# atdh1150usb.net
KiCad netlist of a schematic drawn in EAGLE
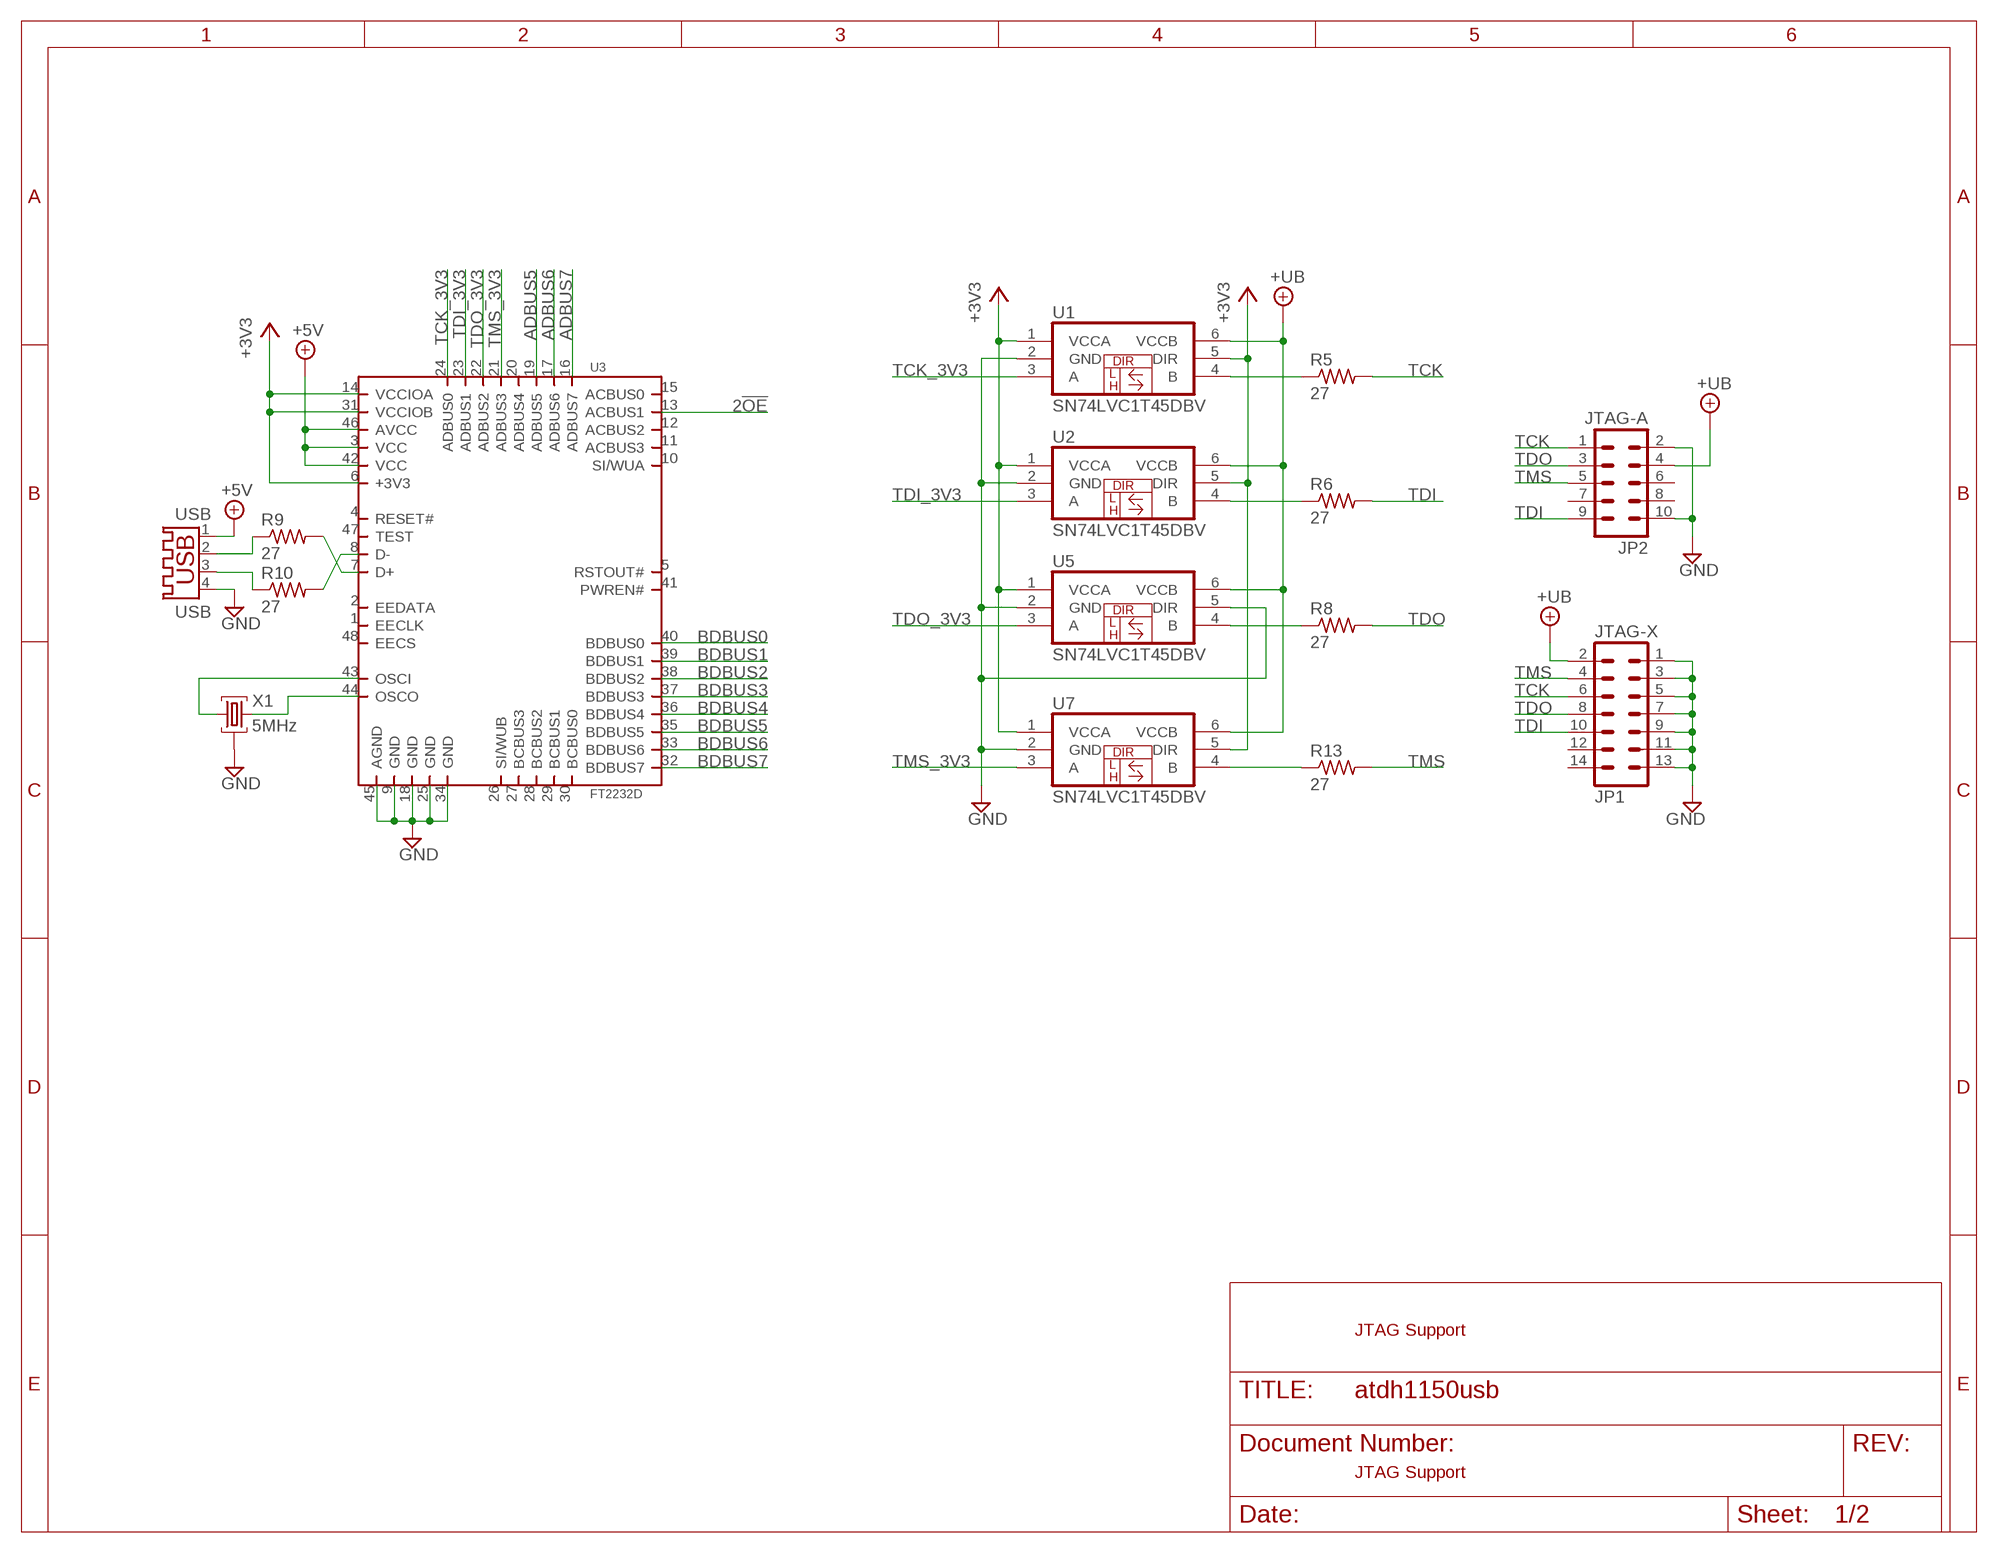
[diagram p0: schematic, sheet 1]
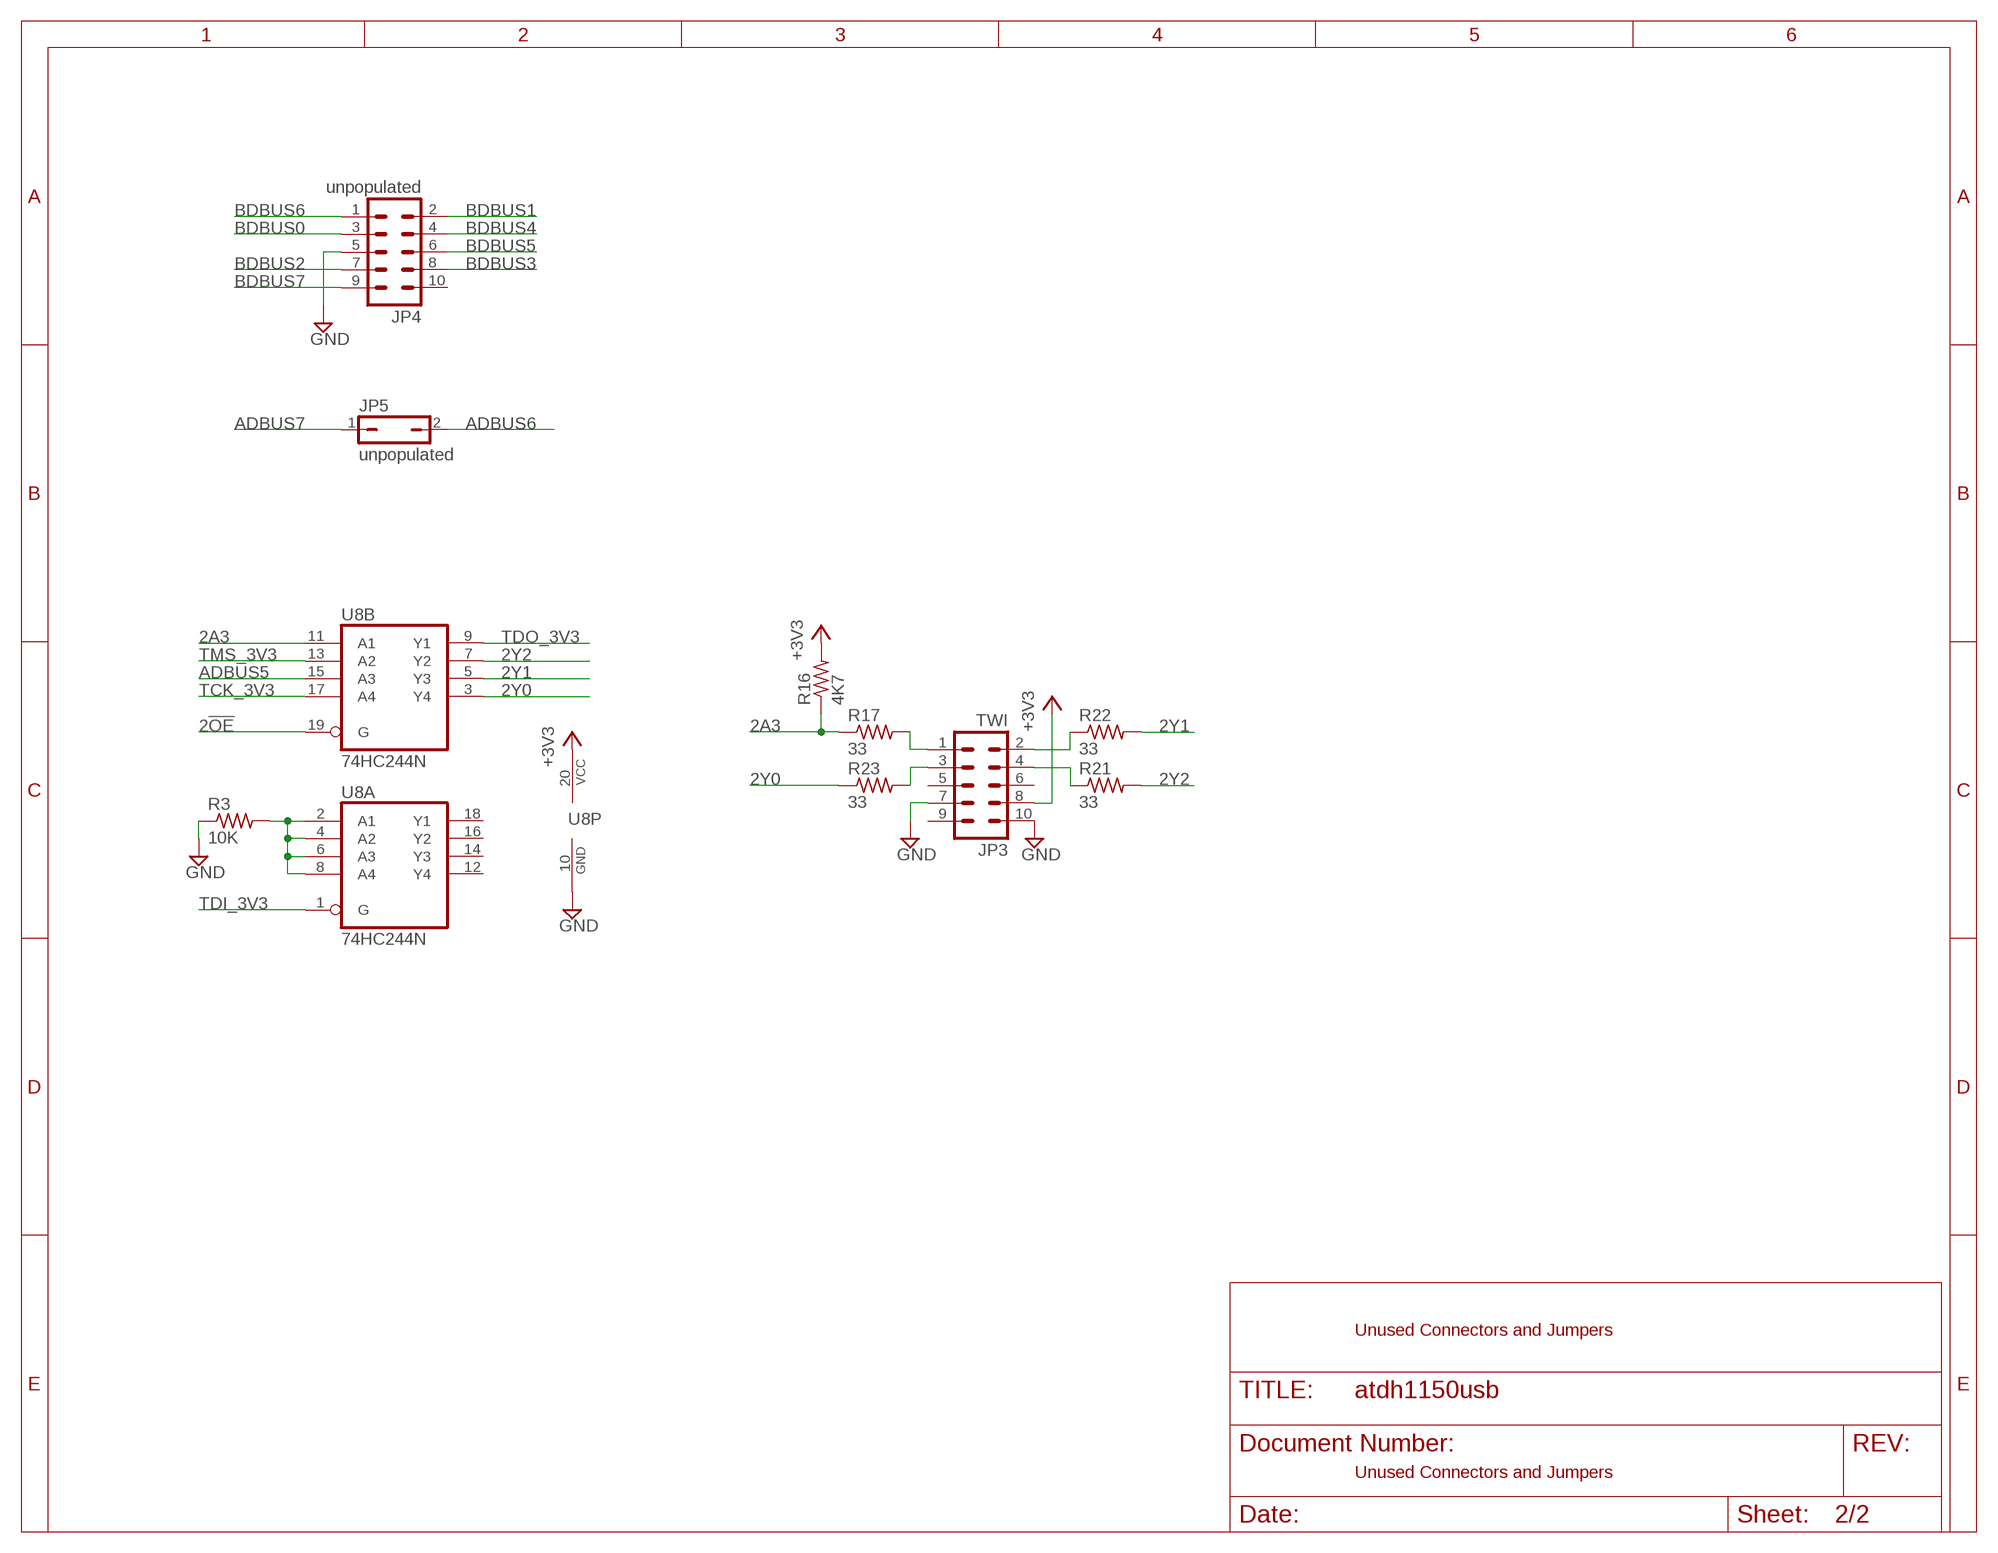
[diagram p1: schematic, sheet 2]

(export (version "E")
  (design (tool "Eeschema 10.0.6"))
  (components
    (comp (ref "JP1")
      (value "JTAG-X")
      (footprint "eagle-import:ML14")
      (libsource (lib "eagle-import") (part "ML14"))
    )
    (comp (ref "JP2")
      (value "JTAG-A")
      (footprint "eagle-import:ML10")
      (libsource (lib "eagle-import") (part "ML10"))
    )
    (comp (ref "R5")
      (value "27")
      (footprint "eagle-import:R0805")
      (libsource (lib "eagle-import") (part "R-US_R0805"))
    )
    (comp (ref "R6")
      (value "27")
      (footprint "eagle-import:R0805")
      (libsource (lib "eagle-import") (part "R-US_R0805"))
    )
    (comp (ref "R8")
      (value "27")
      (footprint "eagle-import:R0805")
      (libsource (lib "eagle-import") (part "R-US_R0805"))
    )
    (comp (ref "R9")
      (value "27")
      (footprint "eagle-import:R0805")
      (libsource (lib "eagle-import") (part "R-US_R0805"))
    )
    (comp (ref "R10")
      (value "27")
      (footprint "eagle-import:R0805")
      (libsource (lib "eagle-import") (part "R-US_R0805"))
    )
    (comp (ref "R13")
      (value "27")
      (footprint "eagle-import:R0805")
      (libsource (lib "eagle-import") (part "R-US_R0805"))
    )
    (comp (ref "U1")
      (value "SN74LVC1T45DBV")
      (footprint "eagle-import:DBV-R-PDSO-G6")
      (libsource (lib "eagle-import") (part "IC_BUFF_SN74LVC1T45DBV"))
    )
    (comp (ref "U2")
      (value "SN74LVC1T45DBV")
      (footprint "eagle-import:DBV-R-PDSO-G6")
      (libsource (lib "eagle-import") (part "IC_BUFF_SN74LVC1T45DBV"))
    )
    (comp (ref "U3")
      (value "FT2232D")
      (footprint "eagle-import:LQFP48")
      (libsource (lib "eagle-import") (part "FT2232D"))
    )
    (comp (ref "U5")
      (value "SN74LVC1T45DBV")
      (footprint "eagle-import:DBV-R-PDSO-G6")
      (libsource (lib "eagle-import") (part "IC_BUFF_SN74LVC1T45DBV"))
    )
    (comp (ref "U7")
      (value "SN74LVC1T45DBV")
      (footprint "eagle-import:DBV-R-PDSO-G6")
      (libsource (lib "eagle-import") (part "IC_BUFF_SN74LVC1T45DBV"))
    )
    (comp (ref "USB")
      (value "USB")
      (footprint "eagle-import:USB-A003")
      (libsource (lib "eagle-import") (part "USB-A003"))
    )
    (comp (ref "X1")
      (value "5MHz")
      (footprint "eagle-import:HC49U")
      (libsource (lib "eagle-import") (part "8M10AHC49T"))
    )
    (comp (ref "JP3")
      (value "TWI")
      (footprint "eagle-import:ML10")
      (libsource (lib "eagle-import") (part "ML10"))
    )
    (comp (ref "JP4")
      (value "unpopulated")
      (footprint "eagle-import:ML10")
      (libsource (lib "eagle-import") (part "ML10"))
    )
    (comp (ref "JP5")
      (value "unpopulated")
      (footprint "eagle-import:JP1")
      (libsource (lib "eagle-import") (part "JP1Q"))
    )
    (comp (ref "R3")
      (value "10K")
      (footprint "eagle-import:R0805")
      (libsource (lib "eagle-import") (part "R-US_R0805"))
    )
    (comp (ref "R16")
      (value "4K7")
      (footprint "eagle-import:R0805")
      (libsource (lib "eagle-import") (part "R-US_R0805"))
    )
    (comp (ref "R17")
      (value "33")
      (footprint "eagle-import:R0805")
      (libsource (lib "eagle-import") (part "R-US_R0805"))
    )
    (comp (ref "R21")
      (value "33")
      (footprint "eagle-import:R0805")
      (libsource (lib "eagle-import") (part "R-US_R0805"))
    )
    (comp (ref "R22")
      (value "33")
      (footprint "eagle-import:R0805")
      (libsource (lib "eagle-import") (part "R-US_R0805"))
    )
    (comp (ref "R23")
      (value "33")
      (footprint "eagle-import:R0805")
      (libsource (lib "eagle-import") (part "R-US_R0805"))
    )
    (comp (ref "U8")
      (value "74HC244N")
      (footprint "eagle-import:DIL20")
      (libsource (lib "eagle-import") (part "74244NLS"))
    )
  )
  (nets
    (net (code "1") (name "+3V3") (class "Default")
      (node (ref "JP3") (pin "8") (pinfunction "8_8") (pintype "passive"))
      (node (ref "R16") (pin "2") (pinfunction "2_2") (pintype "passive"))
      (node (ref "U1") (pin "1") (pinfunction "VCCA_1") (pintype "power_in"))
      (node (ref "U1") (pin "5") (pinfunction "DIR_5") (pintype "input"))
      (node (ref "U2") (pin "1") (pinfunction "VCCA_1") (pintype "power_in"))
      (node (ref "U2") (pin "5") (pinfunction "DIR_5") (pintype "input"))
      (node (ref "U3") (pin "14") (pinfunction "VCCIOA_14") (pintype "power_in"))
      (node (ref "U3") (pin "31") (pinfunction "VCCIOB_31") (pintype "power_in"))
      (node (ref "U3") (pin "6") (pinfunction "+3V3_6") (pintype "power_in"))
      (node (ref "U5") (pin "1") (pinfunction "VCCA_1") (pintype "power_in"))
      (node (ref "U7") (pin "1") (pinfunction "VCCA_1") (pintype "power_in"))
      (node (ref "U7") (pin "5") (pinfunction "DIR_5") (pintype "input"))
      (node (ref "U8") (pin "20") (pinfunction "VCC_20") (pintype "power_in"))
    )
    (net (code "2") (name "+5V") (class "Default")
      (node (ref "U3") (pin "3") (pinfunction "VCC_3") (pintype "power_in"))
      (node (ref "U3") (pin "42") (pinfunction "VCC_42") (pintype "power_in"))
      (node (ref "U3") (pin "46") (pinfunction "AVCC_46") (pintype "power_in"))
      (node (ref "USB") (pin "1") (pinfunction "1_1") (pintype "passive"))
    )
    (net (code "3") (name "+UB") (class "Default")
      (node (ref "JP1") (pin "2") (pinfunction "2_2") (pintype "passive"))
      (node (ref "JP2") (pin "4") (pinfunction "4_4") (pintype "passive"))
      (node (ref "U1") (pin "6") (pinfunction "VCCB_6") (pintype "power_in"))
      (node (ref "U2") (pin "6") (pinfunction "VCCB_6") (pintype "power_in"))
      (node (ref "U5") (pin "6") (pinfunction "VCCB_6") (pintype "power_in"))
      (node (ref "U7") (pin "6") (pinfunction "VCCB_6") (pintype "power_in"))
    )
    (net (code "4") (name "2A3") (class "Default")
      (node (ref "R16") (pin "1") (pinfunction "1_1") (pintype "passive"))
      (node (ref "R17") (pin "1") (pinfunction "1_1") (pintype "passive"))
      (node (ref "U8") (pin "11") (pinfunction "A1_11") (pintype "input"))
    )
    (net (code "5") (name "2Y0") (class "Default")
      (node (ref "R23") (pin "1") (pinfunction "1_1") (pintype "passive"))
      (node (ref "U8") (pin "3") (pinfunction "Y4_3") (pintype "tri_state"))
    )
    (net (code "6") (name "2Y1") (class "Default")
      (node (ref "R22") (pin "2") (pinfunction "2_2") (pintype "passive"))
      (node (ref "U8") (pin "5") (pinfunction "Y3_5") (pintype "tri_state"))
    )
    (net (code "7") (name "2Y2") (class "Default")
      (node (ref "R21") (pin "2") (pinfunction "2_2") (pintype "passive"))
      (node (ref "U8") (pin "7") (pinfunction "Y2_7") (pintype "tri_state"))
    )
    (net (code "8") (name "2~{OE}") (class "Default")
      (node (ref "U3") (pin "13") (pinfunction "ACBUS1_13") (pintype "bidirectional"))
      (node (ref "U8") (pin "19") (pinfunction "G_19") (pintype "input"))
    )
    (net (code "9") (name "ADBUS5") (class "Default")
      (node (ref "U3") (pin "19") (pinfunction "ADBUS5_19") (pintype "bidirectional"))
      (node (ref "U8") (pin "15") (pinfunction "A3_15") (pintype "input"))
    )
    (net (code "10") (name "ADBUS6") (class "Default")
      (node (ref "JP5") (pin "2") (pinfunction "2_2") (pintype "passive"))
      (node (ref "U3") (pin "17") (pinfunction "ADBUS6_17") (pintype "bidirectional"))
    )
    (net (code "11") (name "ADBUS7") (class "Default")
      (node (ref "JP5") (pin "1") (pinfunction "1_1") (pintype "passive"))
      (node (ref "U3") (pin "16") (pinfunction "ADBUS7_16") (pintype "bidirectional"))
    )
    (net (code "12") (name "BDBUS0") (class "Default")
      (node (ref "JP4") (pin "3") (pinfunction "3_3") (pintype "passive"))
      (node (ref "U3") (pin "40") (pinfunction "BDBUS0_40") (pintype "bidirectional"))
    )
    (net (code "13") (name "BDBUS1") (class "Default")
      (node (ref "JP4") (pin "2") (pinfunction "2_2") (pintype "passive"))
      (node (ref "U3") (pin "39") (pinfunction "BDBUS1_39") (pintype "bidirectional"))
    )
    (net (code "14") (name "BDBUS2") (class "Default")
      (node (ref "JP4") (pin "7") (pinfunction "7_7") (pintype "passive"))
      (node (ref "U3") (pin "38") (pinfunction "BDBUS2_38") (pintype "bidirectional"))
    )
    (net (code "15") (name "BDBUS3") (class "Default")
      (node (ref "JP4") (pin "8") (pinfunction "8_8") (pintype "passive"))
      (node (ref "U3") (pin "37") (pinfunction "BDBUS3_37") (pintype "bidirectional"))
    )
    (net (code "16") (name "BDBUS4") (class "Default")
      (node (ref "JP4") (pin "4") (pinfunction "4_4") (pintype "passive"))
      (node (ref "U3") (pin "36") (pinfunction "BDBUS4_36") (pintype "bidirectional"))
    )
    (net (code "17") (name "BDBUS5") (class "Default")
      (node (ref "JP4") (pin "6") (pinfunction "6_6") (pintype "passive"))
      (node (ref "U3") (pin "35") (pinfunction "BDBUS5_35") (pintype "bidirectional"))
    )
    (net (code "18") (name "BDBUS6") (class "Default")
      (node (ref "JP4") (pin "1") (pinfunction "1_1") (pintype "passive"))
      (node (ref "U3") (pin "33") (pinfunction "BDBUS6_33") (pintype "bidirectional"))
    )
    (net (code "19") (name "BDBUS7") (class "Default")
      (node (ref "JP4") (pin "9") (pinfunction "9_9") (pintype "passive"))
      (node (ref "U3") (pin "32") (pinfunction "BDBUS7_32") (pintype "bidirectional"))
    )
    (net (code "20") (name "GND") (class "Default")
      (node (ref "JP1") (pin "1") (pinfunction "1_1") (pintype "passive"))
      (node (ref "JP1") (pin "11") (pinfunction "11_11") (pintype "passive"))
      (node (ref "JP1") (pin "13") (pinfunction "13_13") (pintype "passive"))
      (node (ref "JP1") (pin "3") (pinfunction "3_3") (pintype "passive"))
      (node (ref "JP1") (pin "5") (pinfunction "5_5") (pintype "passive"))
      (node (ref "JP1") (pin "7") (pinfunction "7_7") (pintype "passive"))
      (node (ref "JP1") (pin "9") (pinfunction "9_9") (pintype "passive"))
      (node (ref "JP2") (pin "10") (pinfunction "10_10") (pintype "passive"))
      (node (ref "JP2") (pin "2") (pinfunction "2_2") (pintype "passive"))
      (node (ref "JP3") (pin "10") (pinfunction "10_10") (pintype "passive"))
      (node (ref "JP3") (pin "7") (pinfunction "7_7") (pintype "passive"))
      (node (ref "JP4") (pin "5") (pinfunction "5_5") (pintype "passive"))
      (node (ref "R3") (pin "1") (pinfunction "1_1") (pintype "passive"))
      (node (ref "U1") (pin "2") (pinfunction "GND_2") (pintype "power_in"))
      (node (ref "U2") (pin "2") (pinfunction "GND_2") (pintype "power_in"))
      (node (ref "U3") (pin "18") (pinfunction "GND_18") (pintype "power_in"))
      (node (ref "U3") (pin "25") (pinfunction "GND_25") (pintype "power_in"))
      (node (ref "U3") (pin "34") (pinfunction "GND_34") (pintype "power_in"))
      (node (ref "U3") (pin "45") (pinfunction "AGND_45") (pintype "power_in"))
      (node (ref "U3") (pin "9") (pinfunction "GND_9") (pintype "power_in"))
      (node (ref "U5") (pin "2") (pinfunction "GND_2") (pintype "power_in"))
      (node (ref "U5") (pin "5") (pinfunction "DIR_5") (pintype "input"))
      (node (ref "U7") (pin "2") (pinfunction "GND_2") (pintype "power_in"))
      (node (ref "U8") (pin "10") (pinfunction "GND_10") (pintype "power_in"))
      (node (ref "USB") (pin "4") (pinfunction "4_4") (pintype "passive"))
      (node (ref "X1") (pin "2") (pinfunction "2_2") (pintype "passive"))
    )
    (net (code "21") (name "Net-(JP3-Pad1)") (class "Default")
      (node (ref "JP3") (pin "1") (pinfunction "1_1") (pintype "passive"))
      (node (ref "R17") (pin "2") (pinfunction "2_2") (pintype "passive"))
    )
    (net (code "22") (name "Net-(JP3-Pad2)") (class "Default")
      (node (ref "JP3") (pin "2") (pinfunction "2_2") (pintype "passive"))
      (node (ref "R22") (pin "1") (pinfunction "1_1") (pintype "passive"))
    )
    (net (code "23") (name "Net-(JP3-Pad3)") (class "Default")
      (node (ref "JP3") (pin "3") (pinfunction "3_3") (pintype "passive"))
      (node (ref "R23") (pin "2") (pinfunction "2_2") (pintype "passive"))
    )
    (net (code "24") (name "Net-(JP3-Pad4)") (class "Default")
      (node (ref "JP3") (pin "4") (pinfunction "4_4") (pintype "passive"))
      (node (ref "R21") (pin "1") (pinfunction "1_1") (pintype "passive"))
    )
    (net (code "25") (name "Net-(R9-Pad1)") (class "Default")
      (node (ref "R9") (pin "1") (pinfunction "1_1") (pintype "passive"))
      (node (ref "USB") (pin "2") (pinfunction "2_2") (pintype "passive"))
    )
    (net (code "26") (name "Net-(R10-Pad1)") (class "Default")
      (node (ref "R10") (pin "1") (pinfunction "1_1") (pintype "passive"))
      (node (ref "USB") (pin "3") (pinfunction "3_3") (pintype "passive"))
    )
    (net (code "27") (name "Net-(U1-B)") (class "Default")
      (node (ref "R5") (pin "1") (pinfunction "1_1") (pintype "passive"))
      (node (ref "U1") (pin "4") (pinfunction "B_4") (pintype "bidirectional"))
    )
    (net (code "28") (name "Net-(U2-B)") (class "Default")
      (node (ref "R6") (pin "1") (pinfunction "1_1") (pintype "passive"))
      (node (ref "U2") (pin "4") (pinfunction "B_4") (pintype "bidirectional"))
    )
    (net (code "29") (name "Net-(U3-D+)") (class "Default")
      (node (ref "R9") (pin "2") (pinfunction "2_2") (pintype "passive"))
      (node (ref "U3") (pin "7") (pinfunction "D+_7") (pintype "bidirectional"))
    )
    (net (code "30") (name "Net-(U3-D-)") (class "Default")
      (node (ref "R10") (pin "2") (pinfunction "2_2") (pintype "passive"))
      (node (ref "U3") (pin "8") (pinfunction "D-_8") (pintype "bidirectional"))
    )
    (net (code "31") (name "Net-(U3-OSCI)") (class "Default")
      (node (ref "U3") (pin "43") (pinfunction "OSCI_43") (pintype "input"))
      (node (ref "X1") (pin "1") (pinfunction "1_1") (pintype "passive"))
    )
    (net (code "32") (name "Net-(U3-OSCO)") (class "Default")
      (node (ref "U3") (pin "44") (pinfunction "OSCO_44") (pintype "output"))
      (node (ref "X1") (pin "3") (pinfunction "3_3") (pintype "passive"))
    )
    (net (code "33") (name "Net-(U5-B)") (class "Default")
      (node (ref "R8") (pin "1") (pinfunction "1_1") (pintype "passive"))
      (node (ref "U5") (pin "4") (pinfunction "B_4") (pintype "bidirectional"))
    )
    (net (code "34") (name "Net-(U7-B)") (class "Default")
      (node (ref "R13") (pin "1") (pinfunction "1_1") (pintype "passive"))
      (node (ref "U7") (pin "4") (pinfunction "B_4") (pintype "bidirectional"))
    )
    (net (code "35") (name "Net-(U8A-A1)") (class "Default")
      (node (ref "R3") (pin "2") (pinfunction "2_2") (pintype "passive"))
      (node (ref "U8") (pin "2") (pinfunction "A1_2") (pintype "input"))
      (node (ref "U8") (pin "4") (pinfunction "A2_4") (pintype "input"))
      (node (ref "U8") (pin "6") (pinfunction "A3_6") (pintype "input"))
      (node (ref "U8") (pin "8") (pinfunction "A4_8") (pintype "input"))
    )
    (net (code "36") (name "TCK") (class "Default")
      (node (ref "JP1") (pin "6") (pinfunction "6_6") (pintype "passive"))
      (node (ref "JP2") (pin "1") (pinfunction "1_1") (pintype "passive"))
      (node (ref "R5") (pin "2") (pinfunction "2_2") (pintype "passive"))
    )
    (net (code "37") (name "TCK_3V3") (class "Default")
      (node (ref "U1") (pin "3") (pinfunction "A_3") (pintype "bidirectional"))
      (node (ref "U3") (pin "24") (pinfunction "ADBUS0_24") (pintype "bidirectional"))
      (node (ref "U8") (pin "17") (pinfunction "A4_17") (pintype "input"))
    )
    (net (code "38") (name "TDI") (class "Default")
      (node (ref "JP1") (pin "10") (pinfunction "10_10") (pintype "passive"))
      (node (ref "JP2") (pin "9") (pinfunction "9_9") (pintype "passive"))
      (node (ref "R6") (pin "2") (pinfunction "2_2") (pintype "passive"))
    )
    (net (code "39") (name "TDI_3V3") (class "Default")
      (node (ref "U2") (pin "3") (pinfunction "A_3") (pintype "bidirectional"))
      (node (ref "U3") (pin "23") (pinfunction "ADBUS1_23") (pintype "bidirectional"))
      (node (ref "U8") (pin "1") (pinfunction "G_1") (pintype "input"))
    )
    (net (code "40") (name "TDO") (class "Default")
      (node (ref "JP1") (pin "8") (pinfunction "8_8") (pintype "passive"))
      (node (ref "JP2") (pin "3") (pinfunction "3_3") (pintype "passive"))
      (node (ref "R8") (pin "2") (pinfunction "2_2") (pintype "passive"))
    )
    (net (code "41") (name "TDO_3V3") (class "Default")
      (node (ref "U3") (pin "22") (pinfunction "ADBUS2_22") (pintype "bidirectional"))
      (node (ref "U5") (pin "3") (pinfunction "A_3") (pintype "bidirectional"))
      (node (ref "U8") (pin "9") (pinfunction "Y1_9") (pintype "tri_state"))
    )
    (net (code "42") (name "TMS") (class "Default")
      (node (ref "JP1") (pin "4") (pinfunction "4_4") (pintype "passive"))
      (node (ref "JP2") (pin "5") (pinfunction "5_5") (pintype "passive"))
      (node (ref "R13") (pin "2") (pinfunction "2_2") (pintype "passive"))
    )
    (net (code "43") (name "TMS_3V3") (class "Default")
      (node (ref "U3") (pin "21") (pinfunction "ADBUS3_21") (pintype "bidirectional"))
      (node (ref "U7") (pin "3") (pinfunction "A_3") (pintype "bidirectional"))
      (node (ref "U8") (pin "13") (pinfunction "A2_13") (pintype "input"))
    )
    (net (code "44") (name "unconnected-(JP1-Pad12)") (class "Default")
      (node (ref "JP1") (pin "12") (pinfunction "12_12") (pintype "passive"))
    )
    (net (code "45") (name "unconnected-(JP1-Pad14)") (class "Default")
      (node (ref "JP1") (pin "14") (pinfunction "14_14") (pintype "passive"))
    )
    (net (code "46") (name "unconnected-(JP2-Pad6)") (class "Default")
      (node (ref "JP2") (pin "6") (pinfunction "6_6") (pintype "passive"))
    )
    (net (code "47") (name "unconnected-(JP2-Pad7)") (class "Default")
      (node (ref "JP2") (pin "7") (pinfunction "7_7") (pintype "passive"))
    )
    (net (code "48") (name "unconnected-(JP2-Pad8)") (class "Default")
      (node (ref "JP2") (pin "8") (pinfunction "8_8") (pintype "passive"))
    )
    (net (code "49") (name "unconnected-(JP3-Pad5)") (class "Default")
      (node (ref "JP3") (pin "5") (pinfunction "5_5") (pintype "passive"))
    )
    (net (code "50") (name "unconnected-(JP3-Pad6)") (class "Default")
      (node (ref "JP3") (pin "6") (pinfunction "6_6") (pintype "passive"))
    )
    (net (code "51") (name "unconnected-(JP3-Pad9)") (class "Default")
      (node (ref "JP3") (pin "9") (pinfunction "9_9") (pintype "passive"))
    )
    (net (code "52") (name "unconnected-(JP4-Pad10)") (class "Default")
      (node (ref "JP4") (pin "10") (pinfunction "10_10") (pintype "passive"))
    )
    (net (code "53") (name "unconnected-(U3-ACBUS0-Pad15)") (class "Default")
      (node (ref "U3") (pin "15") (pinfunction "ACBUS0_15") (pintype "bidirectional"))
    )
    (net (code "54") (name "unconnected-(U3-ACBUS2-Pad12)") (class "Default")
      (node (ref "U3") (pin "12") (pinfunction "ACBUS2_12") (pintype "bidirectional"))
    )
    (net (code "55") (name "unconnected-(U3-ACBUS3-Pad11)") (class "Default")
      (node (ref "U3") (pin "11") (pinfunction "ACBUS3_11") (pintype "bidirectional"))
    )
    (net (code "56") (name "unconnected-(U3-ADBUS4-Pad20)") (class "Default")
      (node (ref "U3") (pin "20") (pinfunction "ADBUS4_20") (pintype "bidirectional"))
    )
    (net (code "57") (name "unconnected-(U3-BCBUS0-Pad30)") (class "Default")
      (node (ref "U3") (pin "30") (pinfunction "BCBUS0_30") (pintype "bidirectional"))
    )
    (net (code "58") (name "unconnected-(U3-BCBUS1-Pad29)") (class "Default")
      (node (ref "U3") (pin "29") (pinfunction "BCBUS1_29") (pintype "bidirectional"))
    )
    (net (code "59") (name "unconnected-(U3-BCBUS2-Pad28)") (class "Default")
      (node (ref "U3") (pin "28") (pinfunction "BCBUS2_28") (pintype "bidirectional"))
    )
    (net (code "60") (name "unconnected-(U3-BCBUS3-Pad27)") (class "Default")
      (node (ref "U3") (pin "27") (pinfunction "BCBUS3_27") (pintype "bidirectional"))
    )
    (net (code "61") (name "unconnected-(U3-EECLK-Pad1)") (class "Default")
      (node (ref "U3") (pin "1") (pinfunction "EECLK_1") (pintype "output"))
    )
    (net (code "62") (name "unconnected-(U3-EECS-Pad48)") (class "Default")
      (node (ref "U3") (pin "48") (pinfunction "EECS_48") (pintype "bidirectional"))
    )
    (net (code "63") (name "unconnected-(U3-EEDATA-Pad2)") (class "Default")
      (node (ref "U3") (pin "2") (pinfunction "EEDATA_2") (pintype "bidirectional"))
    )
    (net (code "64") (name "unconnected-(U3-PWREN#-Pad41)") (class "Default")
      (node (ref "U3") (pin "41") (pinfunction "PWREN#_41") (pintype "bidirectional"))
    )
    (net (code "65") (name "unconnected-(U3-RESET#-Pad4)") (class "Default")
      (node (ref "U3") (pin "4") (pinfunction "RESET#_4") (pintype "input"))
    )
    (net (code "66") (name "unconnected-(U3-RSTOUT#-Pad5)") (class "Default")
      (node (ref "U3") (pin "5") (pinfunction "RSTOUT#_5") (pintype "bidirectional"))
    )
    (net (code "67") (name "unconnected-(U3-SI{slash}WUA-Pad10)") (class "Default")
      (node (ref "U3") (pin "10") (pinfunction "SI/WUA_10") (pintype "bidirectional"))
    )
    (net (code "68") (name "unconnected-(U3-SI{slash}WUB-Pad26)") (class "Default")
      (node (ref "U3") (pin "26") (pinfunction "SI/WUB_26") (pintype "bidirectional"))
    )
    (net (code "69") (name "unconnected-(U3-TEST-Pad47)") (class "Default")
      (node (ref "U3") (pin "47") (pinfunction "TEST_47") (pintype "input"))
    )
    (net (code "70") (name "unconnected-(U8A-Y1-Pad18)") (class "Default")
      (node (ref "U8") (pin "18") (pinfunction "Y1_18") (pintype "tri_state"))
    )
    (net (code "71") (name "unconnected-(U8A-Y2-Pad16)") (class "Default")
      (node (ref "U8") (pin "16") (pinfunction "Y2_16") (pintype "tri_state"))
    )
    (net (code "72") (name "unconnected-(U8A-Y3-Pad14)") (class "Default")
      (node (ref "U8") (pin "14") (pinfunction "Y3_14") (pintype "tri_state"))
    )
    (net (code "73") (name "unconnected-(U8A-Y4-Pad12)") (class "Default")
      (node (ref "U8") (pin "12") (pinfunction "Y4_12") (pintype "tri_state"))
    )
  )
)
